# WS2812B_breakout.net
KiCad netlist of a schematic drawn in EAGLE
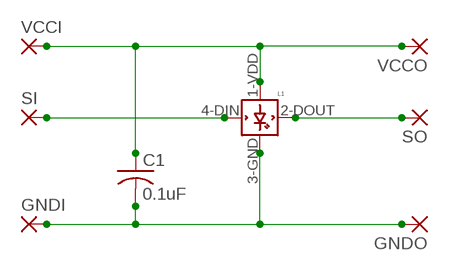
[diagram p0: schematic, sheet 1]

(export (version "E")
  (design (tool "Eeschema 10.0.6"))
  (components
    (comp (ref "C1")
      (value "0.1uF")
      (footprint "eagle-import:C0402K")
      (libsource (lib "eagle-import") (part "C-USC0402K"))
    )
    (comp (ref "GNDI")
      (value "SMD2")
      (footprint "eagle-import:SMD1,27-2,54")
      (libsource (lib "eagle-import") (part "SMD2"))
    )
    (comp (ref "GNDO")
      (value "SMD2")
      (footprint "eagle-import:SMD1,27-2,54")
      (libsource (lib "eagle-import") (part "SMD2"))
    )
    (comp (ref "L1")
      (value "WS2812B")
      (footprint "eagle-import:WS2812B")
      (libsource (lib "eagle-import") (part "WS2812B"))
    )
    (comp (ref "SI")
      (value "SMD2")
      (footprint "eagle-import:SMD1,27-2,54")
      (libsource (lib "eagle-import") (part "SMD2"))
    )
    (comp (ref "SO")
      (value "SMD2")
      (footprint "eagle-import:SMD1,27-2,54")
      (libsource (lib "eagle-import") (part "SMD2"))
    )
    (comp (ref "VCCI")
      (value "SMD2")
      (footprint "eagle-import:SMD1,27-2,54")
      (libsource (lib "eagle-import") (part "SMD2"))
    )
    (comp (ref "VCCO")
      (value "SMD2")
      (footprint "eagle-import:SMD1,27-2,54")
      (libsource (lib "eagle-import") (part "SMD2"))
    )
  )
  (nets
    (net (code "1") (name "Net-(GNDI-P)") (class "Default")
      (node (ref "C1") (pin "2") (pinfunction "2_2") (pintype "passive"))
      (node (ref "GNDI") (pin "1") (pinfunction "P_1") (pintype "passive"))
      (node (ref "GNDO") (pin "1") (pinfunction "P_1") (pintype "passive"))
      (node (ref "L1") (pin "3-GND") (pinfunction "GND_3-GND") (pintype "bidirectional"))
    )
    (net (code "2") (name "Net-(L1-DIN)") (class "Default")
      (node (ref "L1") (pin "4-DIN") (pinfunction "DIN_4-DIN") (pintype "input"))
      (node (ref "SI") (pin "1") (pinfunction "P_1") (pintype "passive"))
    )
    (net (code "3") (name "Net-(L1-DOUT)") (class "Default")
      (node (ref "L1") (pin "2-DOUT") (pinfunction "DOUT_2-DOUT") (pintype "output"))
      (node (ref "SO") (pin "1") (pinfunction "P_1") (pintype "passive"))
    )
    (net (code "4") (name "Net-(L1-VDD)") (class "Default")
      (node (ref "C1") (pin "1") (pinfunction "1_1") (pintype "passive"))
      (node (ref "L1") (pin "1-VDD") (pinfunction "VDD_1-VDD") (pintype "bidirectional"))
      (node (ref "VCCI") (pin "1") (pinfunction "P_1") (pintype "passive"))
      (node (ref "VCCO") (pin "1") (pinfunction "P_1") (pintype "passive"))
    )
  )
)
